# bluz_v2.net
KiCad netlist of a schematic drawn in EAGLE
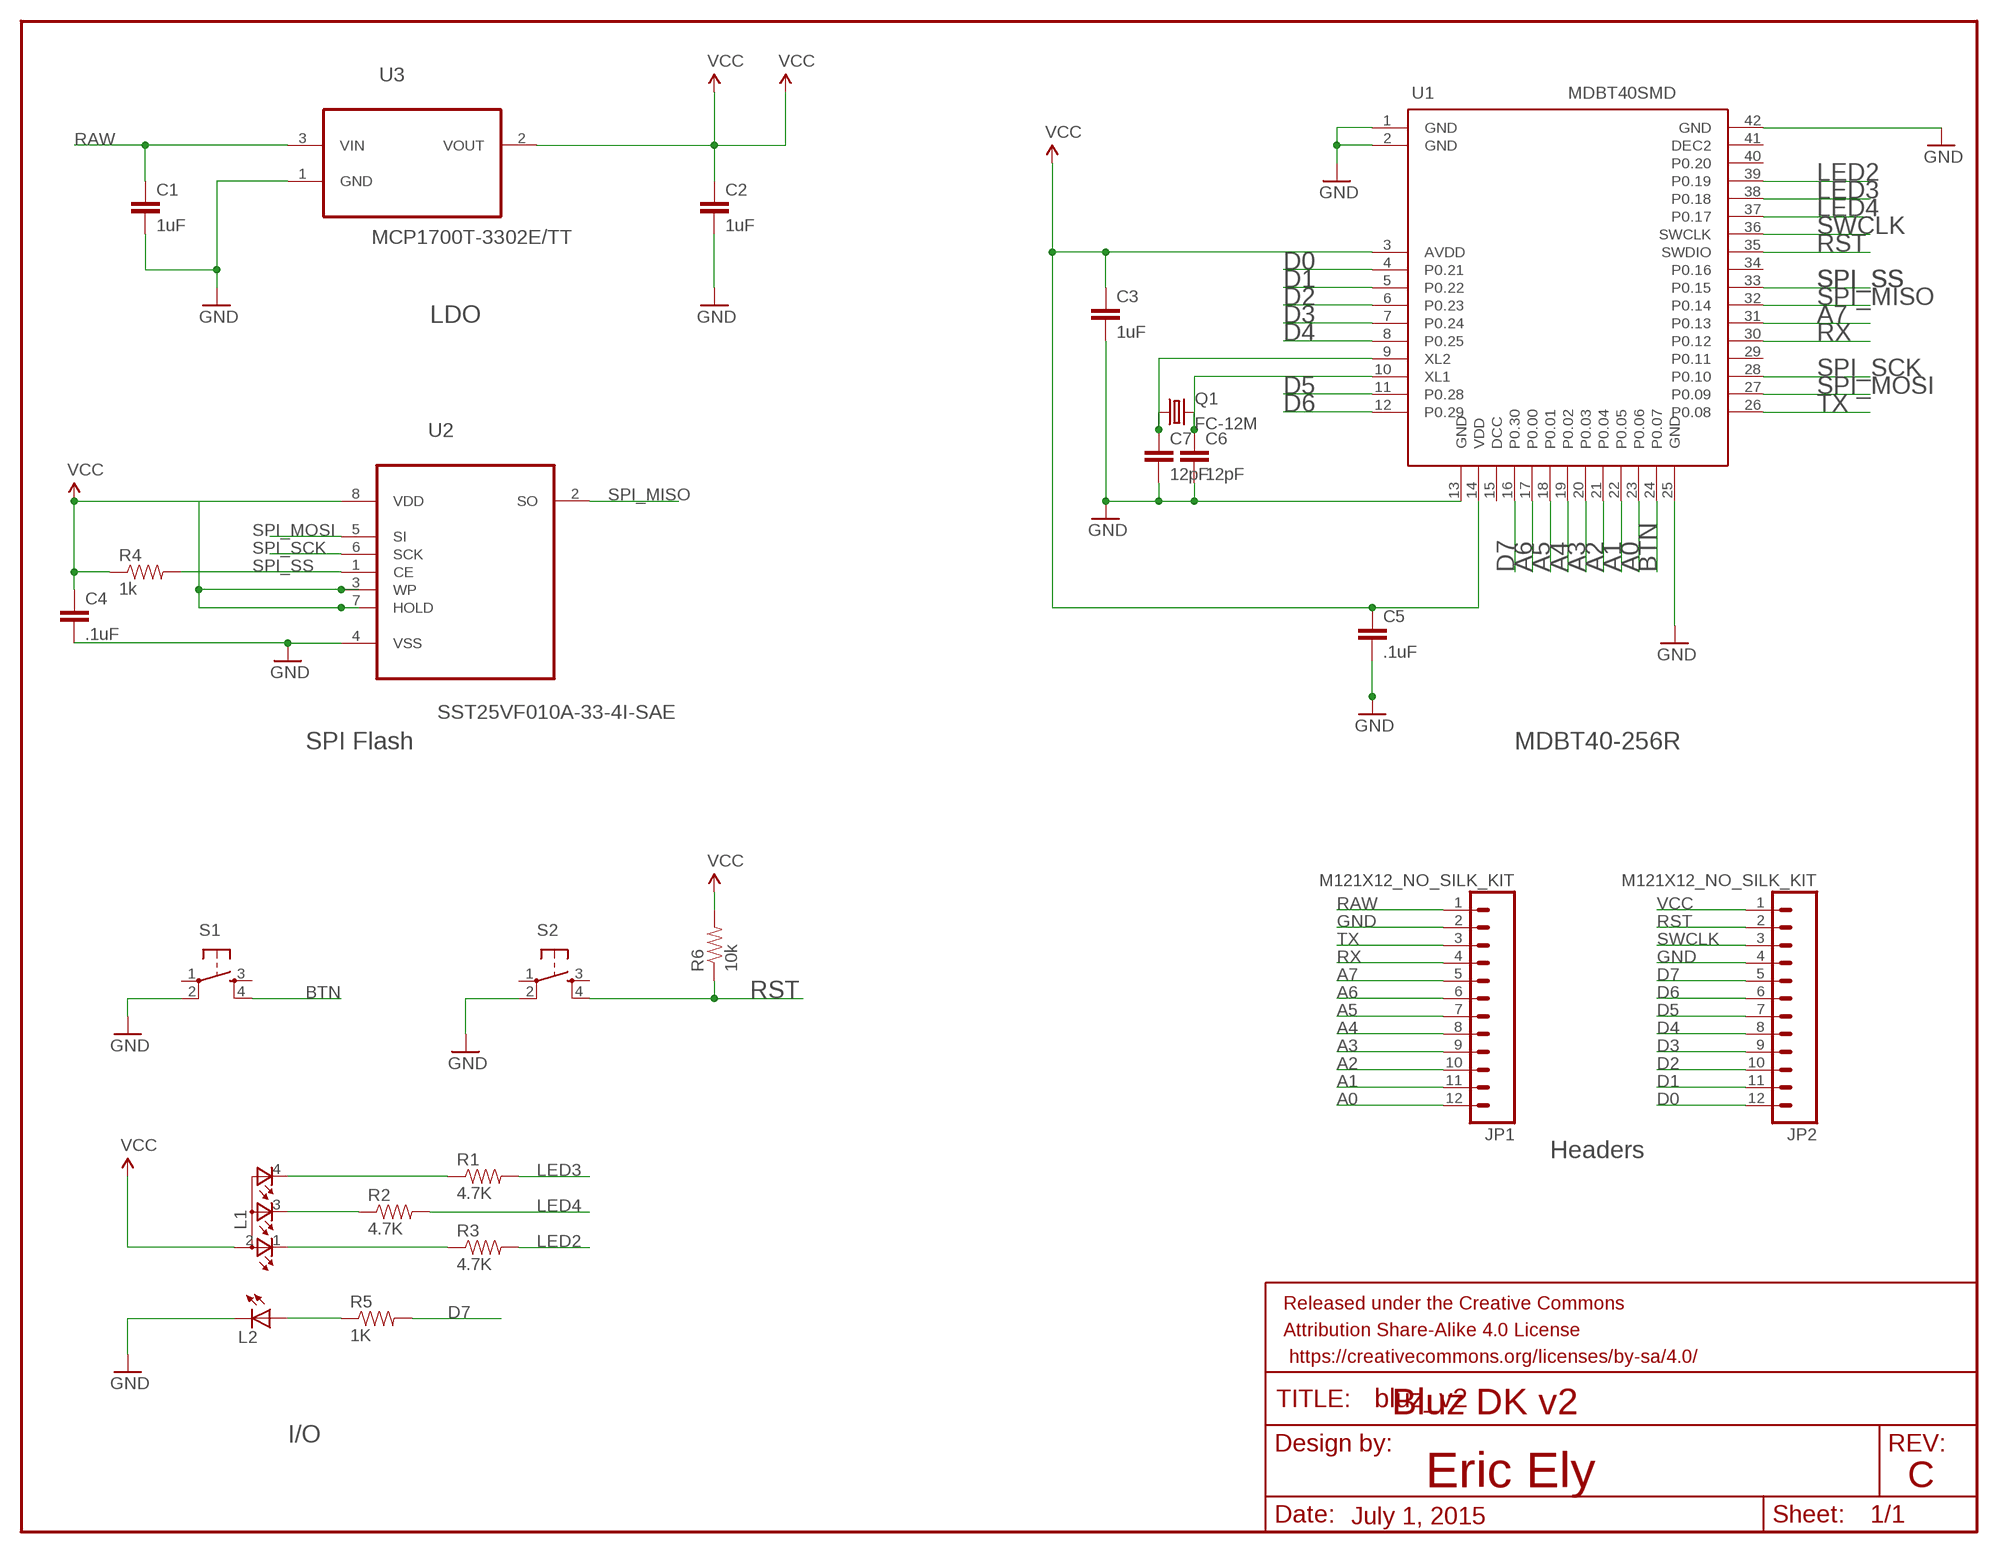
[diagram p0: schematic, sheet 1]

(export (version "E")
  (design (tool "Eeschema 10.0.6"))
  (components
    (comp (ref "C1")
      (value "1uF")
      (footprint "eagle-import:0603-CAP")
      (libsource (lib "eagle-import") (part "CAP0603-CAP"))
    )
    (comp (ref "C2")
      (value "1uF")
      (footprint "eagle-import:0603-CAP")
      (libsource (lib "eagle-import") (part "CAP0603-CAP"))
    )
    (comp (ref "C3")
      (value "1uF")
      (footprint "eagle-import:0603-CAP")
      (libsource (lib "eagle-import") (part "CAP0603-CAP"))
    )
    (comp (ref "C4")
      (value ".1uF")
      (footprint "eagle-import:0603-CAP")
      (libsource (lib "eagle-import") (part "CAP0603-CAP"))
    )
    (comp (ref "C5")
      (value ".1uF")
      (footprint "eagle-import:0603-CAP")
      (libsource (lib "eagle-import") (part "CAP0603-CAP"))
    )
    (comp (ref "C6")
      (value "12pF")
      (footprint "eagle-import:0603-CAP")
      (libsource (lib "eagle-import") (part "CAP0603-CAP"))
    )
    (comp (ref "C7")
      (value "12pF")
      (footprint "eagle-import:0603-CAP")
      (libsource (lib "eagle-import") (part "CAP0603-CAP"))
    )
    (comp (ref "FRAME1")
      (value "FRAME-LETTER")
      (footprint "eagle-import:CREATIVE_COMMONS")
      (libsource (lib "eagle-import") (part "FRAME-LETTER"))
    )
    (comp (ref "JP1")
      (value "M121X12_NO_SILK_KIT")
      (footprint "eagle-import:1X12_NO_SILK_KIT")
      (libsource (lib "eagle-import") (part "M121X12_NO_SILK_KIT"))
    )
    (comp (ref "JP2")
      (value "M121X12_NO_SILK_KIT")
      (footprint "eagle-import:1X12_NO_SILK_KIT")
      (libsource (lib "eagle-import") (part "M121X12_NO_SILK_KIT"))
    )
    (comp (ref "L1")
      (value "TOPLED-3PLCC")
      (footprint "eagle-import:P-LCC-4-3")
      (libsource (lib "eagle-import") (part "TOPLED-3PLCC"))
    )
    (comp (ref "L2")
      (value "LEDCHIP-LED0603")
      (footprint "eagle-import:CHIP-LED0603")
      (libsource (lib "eagle-import") (part "LEDCHIP-LED0603"))
    )
    (comp (ref "Q1")
      (value "FC-12M")
      (footprint "eagle-import:FC-12M")
      (libsource (lib "eagle-import") (part "FC-12M"))
    )
    (comp (ref "R1")
      (value "4.7K")
      (footprint "eagle-import:0603-RES")
      (libsource (lib "eagle-import") (part "RESISTOR0603-RES"))
    )
    (comp (ref "R2")
      (value "4.7K")
      (footprint "eagle-import:0603-RES")
      (libsource (lib "eagle-import") (part "RESISTOR0603-RES"))
    )
    (comp (ref "R3")
      (value "4.7K")
      (footprint "eagle-import:0603-RES")
      (libsource (lib "eagle-import") (part "RESISTOR0603-RES"))
    )
    (comp (ref "R4")
      (value "1k")
      (footprint "eagle-import:0603-RES")
      (libsource (lib "eagle-import") (part "RESISTOR0603"))
    )
    (comp (ref "R5")
      (value "1K")
      (footprint "eagle-import:0603-RES")
      (libsource (lib "eagle-import") (part "RESISTOR0603-RES"))
    )
    (comp (ref "R6")
      (value "10k")
      (footprint "eagle-import:0603-RES")
      (libsource (lib "eagle-import") (part "RESISTOR0603-RES"))
    )
    (comp (ref "S1")
      (value "TAC_SWITCHSMD")
      (footprint "eagle-import:TACTILE_SWITCH_SMD")
      (libsource (lib "eagle-import") (part "TAC_SWITCHSMD"))
    )
    (comp (ref "S2")
      (value "TAC_SWITCHSMD")
      (footprint "eagle-import:TACTILE_SWITCH_SMD")
      (libsource (lib "eagle-import") (part "TAC_SWITCHSMD"))
    )
    (comp (ref "U1")
      (value "MDBT40SMD")
      (footprint "eagle-import:MDBT40")
      (libsource (lib "eagle-import") (part "MDBT40SMD"))
    )
    (comp (ref "U2")
      (value "SST25VF010A-33-4I-SAE")
      (footprint "eagle-import:SOIC127P600X175-8N")
      (libsource (lib "eagle-import") (part "SST25VF010A-33-4I-SAE"))
    )
    (comp (ref "U3")
      (value "MCP1700T-3302E/TT")
      (footprint "eagle-import:SOT95P237X112-3N")
      (libsource (lib "eagle-import") (part "MCP1700T-3302E/TT"))
    )
  )
  (nets
    (net (code "1") (name "/A0") (class "Default")
      (node (ref "JP1") (pin "12") (pinfunction "12_12") (pintype "passive"))
      (node (ref "U1") (pin "23") (pinfunction "P0.06_23") (pintype "bidirectional"))
    )
    (net (code "2") (name "/A1") (class "Default")
      (node (ref "JP1") (pin "11") (pinfunction "11_11") (pintype "passive"))
      (node (ref "U1") (pin "22") (pinfunction "P0.05_22") (pintype "bidirectional"))
    )
    (net (code "3") (name "/A2") (class "Default")
      (node (ref "JP1") (pin "10") (pinfunction "10_10") (pintype "passive"))
      (node (ref "U1") (pin "21") (pinfunction "P0.04_21") (pintype "bidirectional"))
    )
    (net (code "4") (name "/A3") (class "Default")
      (node (ref "JP1") (pin "9") (pinfunction "9_9") (pintype "passive"))
      (node (ref "U1") (pin "20") (pinfunction "P0.03_20") (pintype "bidirectional"))
    )
    (net (code "5") (name "/A4") (class "Default")
      (node (ref "JP1") (pin "8") (pinfunction "8_8") (pintype "passive"))
      (node (ref "U1") (pin "19") (pinfunction "P0.02_19") (pintype "bidirectional"))
    )
    (net (code "6") (name "/A5") (class "Default")
      (node (ref "JP1") (pin "7") (pinfunction "7_7") (pintype "passive"))
      (node (ref "U1") (pin "18") (pinfunction "P0.01_18") (pintype "bidirectional"))
    )
    (net (code "7") (name "/A6") (class "Default")
      (node (ref "JP1") (pin "6") (pinfunction "6_6") (pintype "passive"))
      (node (ref "U1") (pin "17") (pinfunction "P0.00_17") (pintype "bidirectional"))
    )
    (net (code "8") (name "/A7") (class "Default")
      (node (ref "JP1") (pin "5") (pinfunction "5_5") (pintype "passive"))
      (node (ref "U1") (pin "31") (pinfunction "P0.13_31") (pintype "bidirectional"))
    )
    (net (code "9") (name "/BTN") (class "Default")
      (node (ref "S1") (pin "4") (pinfunction "4_4") (pintype "passive"))
      (node (ref "U1") (pin "24") (pinfunction "P0.07_24") (pintype "bidirectional"))
    )
    (net (code "10") (name "/D0") (class "Default")
      (node (ref "JP2") (pin "12") (pinfunction "12_12") (pintype "passive"))
      (node (ref "U1") (pin "4") (pinfunction "P0.21_4") (pintype "bidirectional"))
    )
    (net (code "11") (name "/D1") (class "Default")
      (node (ref "JP2") (pin "11") (pinfunction "11_11") (pintype "passive"))
      (node (ref "U1") (pin "5") (pinfunction "P0.22_5") (pintype "bidirectional"))
    )
    (net (code "12") (name "/D2") (class "Default")
      (node (ref "JP2") (pin "10") (pinfunction "10_10") (pintype "passive"))
      (node (ref "U1") (pin "6") (pinfunction "P0.23_6") (pintype "bidirectional"))
    )
    (net (code "13") (name "/D3") (class "Default")
      (node (ref "JP2") (pin "9") (pinfunction "9_9") (pintype "passive"))
      (node (ref "U1") (pin "7") (pinfunction "P0.24_7") (pintype "bidirectional"))
    )
    (net (code "14") (name "/D4") (class "Default")
      (node (ref "JP2") (pin "8") (pinfunction "8_8") (pintype "passive"))
      (node (ref "U1") (pin "8") (pinfunction "P0.25_8") (pintype "bidirectional"))
    )
    (net (code "15") (name "/D5") (class "Default")
      (node (ref "JP2") (pin "7") (pinfunction "7_7") (pintype "passive"))
      (node (ref "U1") (pin "11") (pinfunction "P0.28_11") (pintype "bidirectional"))
    )
    (net (code "16") (name "/D6") (class "Default")
      (node (ref "JP2") (pin "6") (pinfunction "6_6") (pintype "passive"))
      (node (ref "U1") (pin "12") (pinfunction "P0.29_12") (pintype "bidirectional"))
    )
    (net (code "17") (name "/D7") (class "Default")
      (node (ref "JP2") (pin "5") (pinfunction "5_5") (pintype "passive"))
      (node (ref "R5") (pin "2") (pinfunction "2_2") (pintype "passive"))
      (node (ref "U1") (pin "16") (pinfunction "P0.30_16") (pintype "bidirectional"))
    )
    (net (code "18") (name "/LED2") (class "Default")
      (node (ref "R3") (pin "2") (pinfunction "2_2") (pintype "passive"))
      (node (ref "U1") (pin "39") (pinfunction "P0.19_39") (pintype "bidirectional"))
    )
    (net (code "19") (name "/LED3") (class "Default")
      (node (ref "R1") (pin "2") (pinfunction "2_2") (pintype "passive"))
      (node (ref "U1") (pin "38") (pinfunction "P0.18_38") (pintype "bidirectional"))
    )
    (net (code "20") (name "/LED4") (class "Default")
      (node (ref "R2") (pin "2") (pinfunction "2_2") (pintype "passive"))
      (node (ref "U1") (pin "37") (pinfunction "P0.17_37") (pintype "bidirectional"))
    )
    (net (code "21") (name "/RAW") (class "Default")
      (node (ref "C1") (pin "1") (pinfunction "1_1") (pintype "passive"))
      (node (ref "JP1") (pin "1") (pinfunction "1_1") (pintype "passive"))
      (node (ref "U3") (pin "3") (pinfunction "VIN_3") (pintype "input"))
    )
    (net (code "22") (name "/RST") (class "Default")
      (node (ref "JP2") (pin "2") (pinfunction "2_2") (pintype "passive"))
      (node (ref "R6") (pin "1") (pinfunction "1_1") (pintype "passive"))
      (node (ref "S2") (pin "4") (pinfunction "4_4") (pintype "passive"))
      (node (ref "U1") (pin "35") (pinfunction "SWDIO_35") (pintype "bidirectional"))
    )
    (net (code "23") (name "/RX") (class "Default")
      (node (ref "JP1") (pin "4") (pinfunction "4_4") (pintype "passive"))
      (node (ref "U1") (pin "30") (pinfunction "P0.12_30") (pintype "bidirectional"))
    )
    (net (code "24") (name "/SPI_MISO") (class "Default")
      (node (ref "U1") (pin "32") (pinfunction "P0.14_32") (pintype "bidirectional"))
      (node (ref "U2") (pin "2") (pinfunction "SO_2") (pintype "output"))
    )
    (net (code "25") (name "/SPI_MOSI") (class "Default")
      (node (ref "U1") (pin "27") (pinfunction "P0.09_27") (pintype "bidirectional"))
      (node (ref "U2") (pin "5") (pinfunction "SI_5") (pintype "input"))
    )
    (net (code "26") (name "/SPI_SCK") (class "Default")
      (node (ref "U1") (pin "28") (pinfunction "P0.10_28") (pintype "bidirectional"))
      (node (ref "U2") (pin "6") (pinfunction "SCK_6") (pintype "input"))
    )
    (net (code "27") (name "/SPI_SS") (class "Default")
      (node (ref "R4") (pin "2") (pinfunction "2_2") (pintype "passive"))
      (node (ref "U1") (pin "33") (pinfunction "P0.15_33") (pintype "bidirectional"))
      (node (ref "U2") (pin "1") (pinfunction "CE_1") (pintype "input"))
    )
    (net (code "28") (name "/SWCLK") (class "Default")
      (node (ref "JP2") (pin "3") (pinfunction "3_3") (pintype "passive"))
      (node (ref "U1") (pin "36") (pinfunction "SWCLK_36") (pintype "bidirectional"))
    )
    (net (code "29") (name "/TX") (class "Default")
      (node (ref "JP1") (pin "3") (pinfunction "3_3") (pintype "passive"))
      (node (ref "U1") (pin "26") (pinfunction "P0.08_26") (pintype "bidirectional"))
    )
    (net (code "30") (name "GND") (class "Default")
      (node (ref "C1") (pin "2") (pinfunction "2_2") (pintype "passive"))
      (node (ref "C2") (pin "2") (pinfunction "2_2") (pintype "passive"))
      (node (ref "C3") (pin "2") (pinfunction "2_2") (pintype "passive"))
      (node (ref "C4") (pin "2") (pinfunction "2_2") (pintype "passive"))
      (node (ref "C5") (pin "2") (pinfunction "2_2") (pintype "passive"))
      (node (ref "C6") (pin "2") (pinfunction "2_2") (pintype "passive"))
      (node (ref "C7") (pin "2") (pinfunction "2_2") (pintype "passive"))
      (node (ref "JP1") (pin "2") (pinfunction "2_2") (pintype "passive"))
      (node (ref "JP2") (pin "4") (pinfunction "4_4") (pintype "passive"))
      (node (ref "L2") (pin "C") (pinfunction "C_C") (pintype "passive"))
      (node (ref "S1") (pin "2") (pinfunction "2_2") (pintype "passive"))
      (node (ref "S2") (pin "2") (pinfunction "2_2") (pintype "passive"))
      (node (ref "U1") (pin "1") (pinfunction "GND_1") (pintype "bidirectional"))
      (node (ref "U1") (pin "13") (pinfunction "GND_13") (pintype "bidirectional"))
      (node (ref "U1") (pin "2") (pinfunction "GND_2") (pintype "bidirectional"))
      (node (ref "U1") (pin "25") (pinfunction "GND_25") (pintype "bidirectional"))
      (node (ref "U1") (pin "42") (pinfunction "GND_42") (pintype "bidirectional"))
      (node (ref "U2") (pin "4") (pinfunction "VSS_4") (pintype "passive"))
      (node (ref "U3") (pin "1") (pinfunction "GND_1") (pintype "passive"))
    )
    (net (code "31") (name "Net-(L1-CBLUE)") (class "Default")
      (node (ref "L1") (pin "3") (pinfunction "CBLUE_3") (pintype "passive"))
      (node (ref "R2") (pin "1") (pinfunction "1_1") (pintype "passive"))
    )
    (net (code "32") (name "Net-(L1-CGREEN)") (class "Default")
      (node (ref "L1") (pin "4") (pinfunction "CGREEN_4") (pintype "passive"))
      (node (ref "R1") (pin "1") (pinfunction "1_1") (pintype "passive"))
    )
    (net (code "33") (name "Net-(L1-CRED)") (class "Default")
      (node (ref "L1") (pin "1") (pinfunction "CRED_1") (pintype "passive"))
      (node (ref "R3") (pin "1") (pinfunction "1_1") (pintype "passive"))
    )
    (net (code "34") (name "Net-(L2-PadA)") (class "Default")
      (node (ref "L2") (pin "A") (pinfunction "A_A") (pintype "passive"))
      (node (ref "R5") (pin "1") (pinfunction "1_1") (pintype "passive"))
    )
    (net (code "35") (name "Net-(U1-XL1)") (class "Default")
      (node (ref "C6") (pin "1") (pinfunction "1_1") (pintype "passive"))
      (node (ref "Q1") (pin "2") (pinfunction "2_2") (pintype "passive"))
      (node (ref "U1") (pin "10") (pinfunction "XL1_10") (pintype "bidirectional"))
    )
    (net (code "36") (name "Net-(U1-XL2)") (class "Default")
      (node (ref "C7") (pin "1") (pinfunction "1_1") (pintype "passive"))
      (node (ref "Q1") (pin "1") (pinfunction "1_1") (pintype "passive"))
      (node (ref "U1") (pin "9") (pinfunction "XL2_9") (pintype "bidirectional"))
    )
    (net (code "37") (name "VCC") (class "Default")
      (node (ref "C2") (pin "1") (pinfunction "1_1") (pintype "passive"))
      (node (ref "C3") (pin "1") (pinfunction "1_1") (pintype "passive"))
      (node (ref "C4") (pin "1") (pinfunction "1_1") (pintype "passive"))
      (node (ref "C5") (pin "1") (pinfunction "1_1") (pintype "passive"))
      (node (ref "JP2") (pin "1") (pinfunction "1_1") (pintype "passive"))
      (node (ref "L1") (pin "2") (pinfunction "A2_2") (pintype "passive"))
      (node (ref "R4") (pin "1") (pinfunction "1_1") (pintype "passive"))
      (node (ref "R6") (pin "2") (pinfunction "2_2") (pintype "passive"))
      (node (ref "U1") (pin "14") (pinfunction "VDD_14") (pintype "bidirectional"))
      (node (ref "U1") (pin "3") (pinfunction "AVDD_3") (pintype "bidirectional"))
      (node (ref "U2") (pin "3") (pinfunction "WP_3") (pintype "input"))
      (node (ref "U2") (pin "7") (pinfunction "HOLD_7") (pintype "input"))
      (node (ref "U2") (pin "8") (pinfunction "VDD_8") (pintype "power_in"))
      (node (ref "U3") (pin "2") (pinfunction "VOUT_2") (pintype "output"))
    )
    (net (code "38") (name "unconnected-(S1-Pad1)") (class "Default")
      (node (ref "S1") (pin "1") (pinfunction "1_1") (pintype "passive"))
    )
    (net (code "39") (name "unconnected-(S1-Pad3)") (class "Default")
      (node (ref "S1") (pin "3") (pinfunction "3_3") (pintype "passive"))
    )
    (net (code "40") (name "unconnected-(S2-Pad1)") (class "Default")
      (node (ref "S2") (pin "1") (pinfunction "1_1") (pintype "passive"))
    )
    (net (code "41") (name "unconnected-(S2-Pad3)") (class "Default")
      (node (ref "S2") (pin "3") (pinfunction "3_3") (pintype "passive"))
    )
    (net (code "42") (name "unconnected-(U1-DCC-Pad15)") (class "Default")
      (node (ref "U1") (pin "15") (pinfunction "DCC_15") (pintype "bidirectional"))
    )
    (net (code "43") (name "unconnected-(U1-DEC2-Pad41)") (class "Default")
      (node (ref "U1") (pin "41") (pinfunction "DEC2_41") (pintype "bidirectional"))
    )
    (net (code "44") (name "unconnected-(U1-P0.11-Pad29)") (class "Default")
      (node (ref "U1") (pin "29") (pinfunction "P0.11_29") (pintype "bidirectional"))
    )
    (net (code "45") (name "unconnected-(U1-P0.16-Pad34)") (class "Default")
      (node (ref "U1") (pin "34") (pinfunction "P0.16_34") (pintype "bidirectional"))
    )
    (net (code "46") (name "unconnected-(U1-P0.20-Pad40)") (class "Default")
      (node (ref "U1") (pin "40") (pinfunction "P0.20_40") (pintype "bidirectional"))
    )
  )
)
